# w5500.net
KiCad netlist of a schematic drawn in Altium Designer
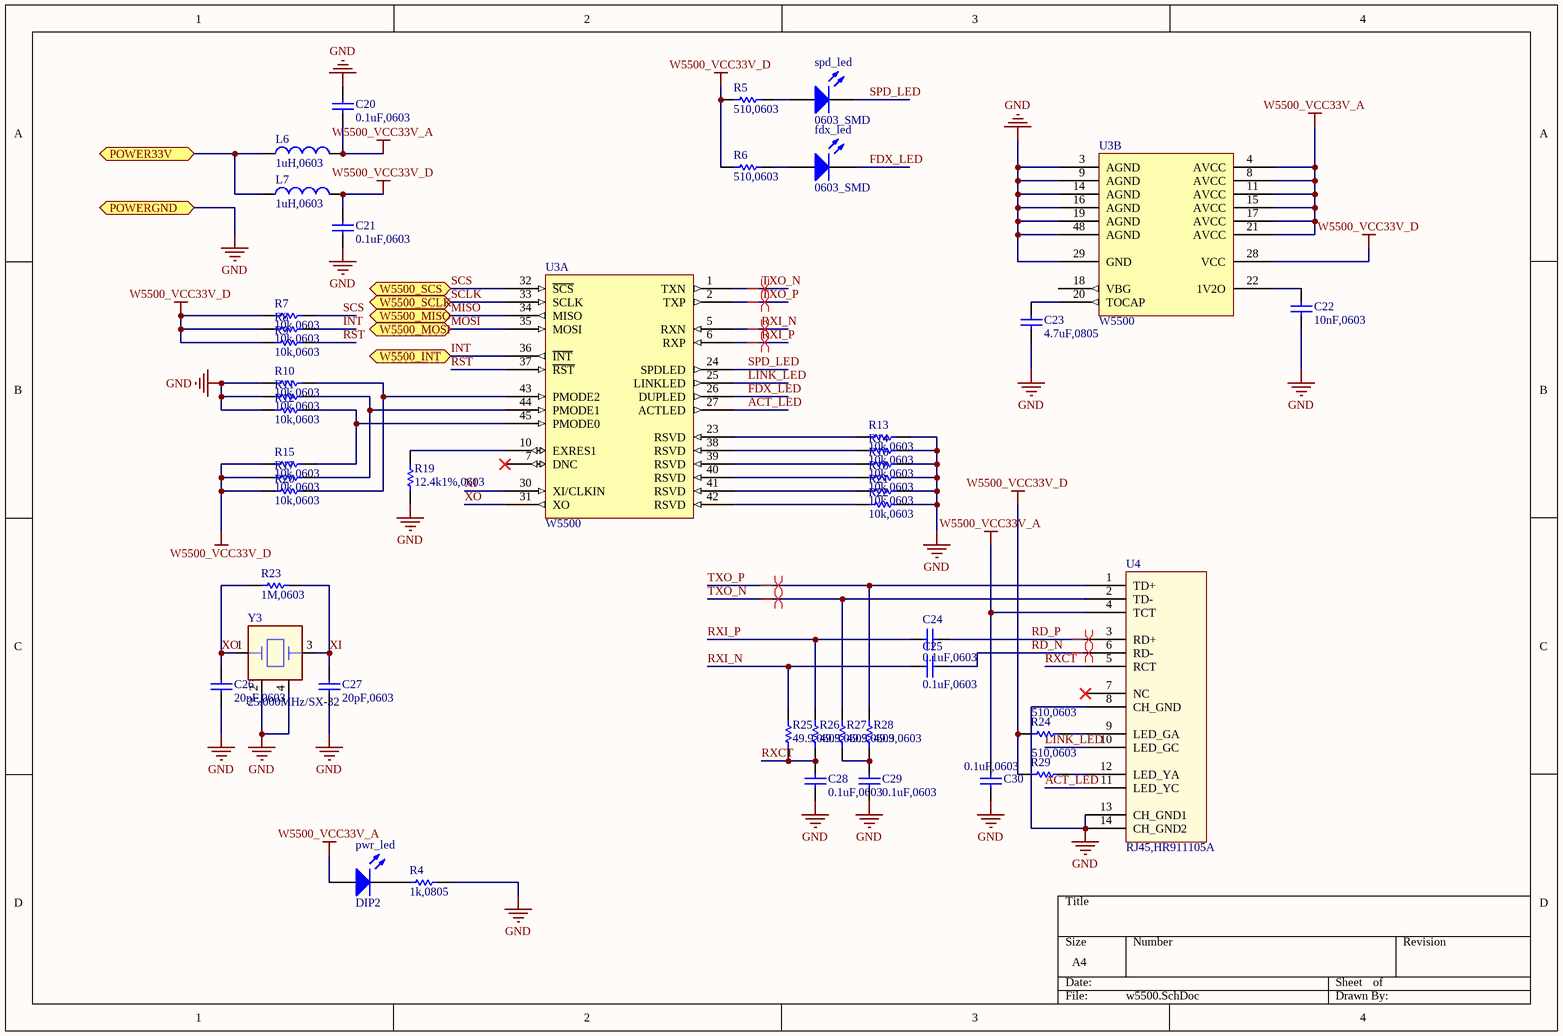
[diagram p0: w5500.SchDoc]

(export (version "E")
  (design (tool "Eeschema 10.0.6"))
  (components
    (comp (ref "C20")
      (value "0.1uF,0603")
      (footprint "C0603")
      (description "Capacitor")
      (fields (field (name "PUBLISHER") "Altium Limited"))
      (libsource (lib "Inte") (part "CAP"))
    )
    (comp (ref "C21")
      (value "0.1uF,0603")
      (footprint "C0603")
      (description "Capacitor")
      (fields (field (name "PUBLISHER") "Altium Limited"))
      (libsource (lib "Inte") (part "CAP"))
    )
    (comp (ref "C22")
      (value "10nF,0603")
      (footprint "C0603")
      (description "Capacitor")
      (fields (field (name "PUBLISHER") "Altium Limited"))
      (libsource (lib "Inte") (part "CAP"))
    )
    (comp (ref "C23")
      (value "4.7uF,0805")
      (footprint "C0805")
      (description "Capacitor")
      (fields (field (name "PUBLISHER") "Altium Limited"))
      (libsource (lib "Inte") (part "CAP"))
    )
    (comp (ref "C24")
      (value "0.1uF,0603")
      (footprint "C0603")
      (description "Capacitor")
      (fields (field (name "PUBLISHER") "Altium Limited"))
      (libsource (lib "Inte") (part "CAP"))
    )
    (comp (ref "C25")
      (value "0.1uF,0603")
      (footprint "C0603")
      (description "Capacitor")
      (fields (field (name "PUBLISHER") "Altium Limited"))
      (libsource (lib "Inte") (part "CAP"))
    )
    (comp (ref "C26")
      (value "20pF,0603")
      (footprint "C0603")
      (description "Capacitor")
      (fields (field (name "PUBLISHER") "Altium Limited"))
      (libsource (lib "Inte") (part "CAP"))
    )
    (comp (ref "C27")
      (value "20pF,0603")
      (footprint "C0603")
      (description "Capacitor")
      (fields (field (name "PUBLISHER") "Altium Limited"))
      (libsource (lib "Inte") (part "CAP"))
    )
    (comp (ref "C28")
      (value "0.1uF,0603")
      (footprint "C0603")
      (description "Capacitor")
      (fields (field (name "PUBLISHER") "Altium Limited"))
      (libsource (lib "Inte") (part "CAP"))
    )
    (comp (ref "C29")
      (value "0.1uF,0603")
      (footprint "C0603")
      (description "Capacitor")
      (fields (field (name "PUBLISHER") "Altium Limited"))
      (libsource (lib "Inte") (part "CAP"))
    )
    (comp (ref "C30")
      (value "0.1uF,0603")
      (footprint "C0603")
      (description "Capacitor")
      (fields (field (name "PUBLISHER") "Altium Limited"))
      (libsource (lib "Inte") (part "CAP"))
    )
    (comp (ref "fdx_led")
      (value "0603_SMD")
      (footprint "LED0805")
      (description "led")
      (libsource (lib "Inte") (part "LED"))
    )
    (comp (ref "L6")
      (value "1uH,0603")
      (footprint "L0603")
      (description "Inductor")
      (fields (field (name "PUBLISHER") "Altium Limited"))
      (libsource (lib "Inte") (part "Inductor"))
    )
    (comp (ref "L7")
      (value "1uH,0603")
      (footprint "L0603")
      (description "Inductor")
      (fields (field (name "PUBLISHER") "Altium Limited"))
      (libsource (lib "Inte") (part "Inductor"))
    )
    (comp (ref "pwr_led") (value "DIP2") (footprint "LEDDIP2") (libsource (lib "Inte") (part "LED")))
    (comp (ref "R4")
      (value "1k,0805")
      (footprint "R0805")
      (description "Resistor")
      (fields (field (name "PUBLISHER") "Altium Limited"))
      (libsource (lib "Inte") (part "Res1"))
    )
    (comp (ref "R5")
      (value "510,0603")
      (footprint "R0603")
      (description "Resistor")
      (fields (field (name "PUBLISHER") "Altium Limited"))
      (libsource (lib "Inte") (part "Res1"))
    )
    (comp (ref "R6")
      (value "510,0603")
      (footprint "R0603")
      (description "Resistor")
      (fields (field (name "PUBLISHER") "Altium Limited"))
      (libsource (lib "Inte") (part "Res1"))
    )
    (comp (ref "R7")
      (value "10k,0603")
      (footprint "R0603")
      (description "Resistor")
      (fields (field (name "PUBLISHER") "Altium Limited"))
      (libsource (lib "Inte") (part "Res1"))
    )
    (comp (ref "R8")
      (value "10k,0603")
      (footprint "R0603")
      (description "Resistor")
      (fields (field (name "PUBLISHER") "Altium Limited"))
      (libsource (lib "Inte") (part "Res1"))
    )
    (comp (ref "R9")
      (value "10k,0603")
      (footprint "R0603")
      (description "Resistor")
      (fields (field (name "PUBLISHER") "Altium Limited"))
      (libsource (lib "Inte") (part "Res1"))
    )
    (comp (ref "R10")
      (value "10k,0603")
      (footprint "R0603")
      (description "Resistor")
      (fields (field (name "PUBLISHER") "Altium Limited"))
      (libsource (lib "Inte") (part "Res1"))
    )
    (comp (ref "R11")
      (value "10k,0603")
      (footprint "R0603")
      (description "Resistor")
      (fields (field (name "PUBLISHER") "Altium Limited"))
      (libsource (lib "Inte") (part "Res1"))
    )
    (comp (ref "R12")
      (value "10k,0603")
      (footprint "R0603")
      (description "Resistor")
      (fields (field (name "PUBLISHER") "Altium Limited"))
      (libsource (lib "Inte") (part "Res1"))
    )
    (comp (ref "R13")
      (value "10k,0603")
      (footprint "R0603")
      (description "Resistor")
      (fields (field (name "PUBLISHER") "Altium Limited"))
      (libsource (lib "Inte") (part "Res1"))
    )
    (comp (ref "R14")
      (value "10k,0603")
      (footprint "R0603")
      (description "Resistor")
      (fields (field (name "PUBLISHER") "Altium Limited"))
      (libsource (lib "Inte") (part "Res1"))
    )
    (comp (ref "R15")
      (value "10k,0603")
      (footprint "R0603")
      (description "Resistor")
      (fields (field (name "PUBLISHER") "Altium Limited"))
      (libsource (lib "Inte") (part "Res1"))
    )
    (comp (ref "R16")
      (value "10k,0603")
      (footprint "R0603")
      (description "Resistor")
      (fields (field (name "PUBLISHER") "Altium Limited"))
      (libsource (lib "Inte") (part "Res1"))
    )
    (comp (ref "R17")
      (value "10k,0603")
      (footprint "R0603")
      (description "Resistor")
      (fields (field (name "PUBLISHER") "Altium Limited"))
      (libsource (lib "Inte") (part "Res1"))
    )
    (comp (ref "R18")
      (value "10k,0603")
      (footprint "R0603")
      (description "Resistor")
      (fields (field (name "PUBLISHER") "Altium Limited"))
      (libsource (lib "Inte") (part "Res1"))
    )
    (comp (ref "R19")
      (value "12.4k1%,0603")
      (footprint "R0603")
      (description "Resistor")
      (fields (field (name "PUBLISHER") "Altium Limited"))
      (libsource (lib "Inte") (part "Res1"))
    )
    (comp (ref "R20")
      (value "10k,0603")
      (footprint "R0603")
      (description "Resistor")
      (fields (field (name "PUBLISHER") "Altium Limited"))
      (libsource (lib "Inte") (part "Res1"))
    )
    (comp (ref "R21")
      (value "10k,0603")
      (footprint "R0603")
      (description "Resistor")
      (fields (field (name "PUBLISHER") "Altium Limited"))
      (libsource (lib "Inte") (part "Res1"))
    )
    (comp (ref "R22")
      (value "10k,0603")
      (footprint "R0603")
      (description "Resistor")
      (fields (field (name "PUBLISHER") "Altium Limited"))
      (libsource (lib "Inte") (part "Res1"))
    )
    (comp (ref "R23")
      (value "1M,0603")
      (footprint "R0603")
      (description "Resistor")
      (fields (field (name "PUBLISHER") "Altium Limited"))
      (libsource (lib "Inte") (part "Res1"))
    )
    (comp (ref "R24")
      (value "510,0603")
      (footprint "R0603")
      (description "Resistor")
      (fields (field (name "PUBLISHER") "Altium Limited"))
      (libsource (lib "Inte") (part "Res1"))
    )
    (comp (ref "R25")
      (value "49.9,0603")
      (footprint "R0603")
      (description "Resistor")
      (fields (field (name "PUBLISHER") "Altium Limited"))
      (libsource (lib "Inte") (part "Res1"))
    )
    (comp (ref "R26")
      (value "49.9,0603")
      (footprint "R0603")
      (description "Resistor")
      (fields (field (name "PUBLISHER") "Altium Limited"))
      (libsource (lib "Inte") (part "Res1"))
    )
    (comp (ref "R27")
      (value "49.9,0603")
      (footprint "R0603")
      (description "Resistor")
      (fields (field (name "PUBLISHER") "Altium Limited"))
      (libsource (lib "Inte") (part "Res1"))
    )
    (comp (ref "R28")
      (value "49.9,0603")
      (footprint "R0603")
      (description "Resistor")
      (fields (field (name "PUBLISHER") "Altium Limited"))
      (libsource (lib "Inte") (part "Res1"))
    )
    (comp (ref "R29")
      (value "510,0603")
      (footprint "R0603")
      (description "Resistor")
      (fields (field (name "PUBLISHER") "Altium Limited"))
      (libsource (lib "Inte") (part "Res1"))
    )
    (comp (ref "spd_led")
      (value "0603_SMD")
      (footprint "LED0805")
      (description "led")
      (libsource (lib "Inte") (part "LED"))
    )
    (comp (ref "U3") (value "W5500") (footprint "LQFP48") (libsource (lib "Inte") (part "W5500")))
    (comp (ref "U4") (value "RJ45,HR911105A") (footprint "RJ45") (libsource (lib "Inte") (part "HR911105A")))
    (comp (ref "Y3") (value "25.000MHz/SX-32") (footprint "3225") (libsource (lib "Inte") (part "CRYSTAL_5")))
  )
  (nets
    (net (code "1") (name "/ACT_LED") (class "Default")
      (node (ref "U3") (pin "27") (pinfunction "ACTLED_27") (pintype "output"))
      (node (ref "U4") (pin "11") (pinfunction "LED_YC_11") (pintype "passive"))
    )
    (net (code "2") (name "/FDX_LED") (class "Default")
      (node (ref "U3") (pin "26") (pinfunction "DUPLED_26") (pintype "output"))
      (node (ref "fdx_led") (pin "2") (pinfunction "K_2") (pintype "passive"))
    )
    (net (code "3") (name "/INT") (class "Default")
      (node (ref "R8") (pin "2") (pinfunction "2_2") (pintype "passive"))
      (node (ref "U3") (pin "36") (pinfunction "~{INT}_36") (pintype "output"))
    )
    (net (code "4") (name "/LINK_LED") (class "Default")
      (node (ref "U3") (pin "25") (pinfunction "LINKLED_25") (pintype "output"))
      (node (ref "U4") (pin "10") (pinfunction "LED_GC_10") (pintype "passive"))
    )
    (net (code "5") (name "/MISO") (class "Default")
      (node (ref "U3") (pin "34") (pinfunction "MISO_34") (pintype "output"))
    )
    (net (code "6") (name "/MOSI") (class "Default")
      (node (ref "U3") (pin "35") (pinfunction "MOSI_35") (pintype "input"))
    )
    (net (code "7") (name "/POWER33V") (class "Default")
      (node (ref "L6") (pin "1") (pinfunction "1_1") (pintype "passive"))
      (node (ref "L7") (pin "1") (pinfunction "1_1") (pintype "passive"))
    )
    (net (code "8") (name "/RD_N") (class "Default")
      (node (ref "C25") (pin "2") (pinfunction "2_2") (pintype "passive"))
      (node (ref "U4") (pin "6") (pinfunction "RD-_6") (pintype "passive"))
    )
    (net (code "9") (name "/RD_P") (class "Default")
      (node (ref "C24") (pin "2") (pinfunction "2_2") (pintype "passive"))
      (node (ref "U4") (pin "3") (pinfunction "RD+_3") (pintype "passive"))
    )
    (net (code "10") (name "/RST") (class "Default")
      (node (ref "R9") (pin "2") (pinfunction "2_2") (pintype "passive"))
      (node (ref "U3") (pin "37") (pinfunction "~{RST}_37") (pintype "input"))
    )
    (net (code "11") (name "/RXCT") (class "Default")
      (node (ref "C28") (pin "2") (pinfunction "2_2") (pintype "passive"))
      (node (ref "R25") (pin "1") (pinfunction "1_1") (pintype "passive"))
      (node (ref "R26") (pin "2") (pinfunction "2_2") (pintype "passive"))
      (node (ref "U4") (pin "5") (pinfunction "RCT_5") (pintype "passive"))
    )
    (net (code "12") (name "/RXI_N") (class "Default")
      (node (ref "C25") (pin "1") (pinfunction "1_1") (pintype "passive"))
      (node (ref "R25") (pin "2") (pinfunction "2_2") (pintype "passive"))
      (node (ref "U3") (pin "5") (pinfunction "RXN_5") (pintype "input"))
    )
    (net (code "13") (name "/RXI_P") (class "Default")
      (node (ref "C24") (pin "1") (pinfunction "1_1") (pintype "passive"))
      (node (ref "R26") (pin "1") (pinfunction "1_1") (pintype "passive"))
      (node (ref "U3") (pin "6") (pinfunction "RXP_6") (pintype "input"))
    )
    (net (code "14") (name "/SCLK") (class "Default")
      (node (ref "U3") (pin "33") (pinfunction "SCLK_33") (pintype "input"))
    )
    (net (code "15") (name "/SCS") (class "Default")
      (node (ref "R7") (pin "2") (pinfunction "2_2") (pintype "passive"))
      (node (ref "U3") (pin "32") (pinfunction "~{SCS}_32") (pintype "input"))
    )
    (net (code "16") (name "/SPD_LED") (class "Default")
      (node (ref "U3") (pin "24") (pinfunction "SPDLED_24") (pintype "output"))
      (node (ref "spd_led") (pin "2") (pinfunction "K_2") (pintype "passive"))
    )
    (net (code "17") (name "/TXO_N") (class "Default")
      (node (ref "R27") (pin "1") (pinfunction "1_1") (pintype "passive"))
      (node (ref "U3") (pin "1") (pinfunction "TXN_1") (pintype "output"))
      (node (ref "U4") (pin "2") (pinfunction "TD-_2") (pintype "passive"))
    )
    (net (code "18") (name "/TXO_P") (class "Default")
      (node (ref "R28") (pin "1") (pinfunction "1_1") (pintype "passive"))
      (node (ref "U3") (pin "2") (pinfunction "TXP_2") (pintype "output"))
      (node (ref "U4") (pin "1") (pinfunction "TD+_1") (pintype "passive"))
    )
    (net (code "19") (name "/XI") (class "Default")
      (node (ref "C27") (pin "1") (pinfunction "1_1") (pintype "passive"))
      (node (ref "R23") (pin "2") (pinfunction "2_2") (pintype "passive"))
      (node (ref "U3") (pin "30") (pinfunction "XI/CLKIN_30") (pintype "input"))
      (node (ref "Y3") (pin "3") (pinfunction "3_3") (pintype "passive"))
    )
    (net (code "20") (name "/XO") (class "Default")
      (node (ref "C26") (pin "1") (pinfunction "1_1") (pintype "passive"))
      (node (ref "R23") (pin "1") (pinfunction "1_1") (pintype "passive"))
      (node (ref "U3") (pin "31") (pinfunction "XO_31") (pintype "output"))
      (node (ref "Y3") (pin "1") (pinfunction "1_1") (pintype "passive"))
    )
    (net (code "21") (name "GND") (class "Default")
      (node (ref "C20") (pin "2") (pinfunction "2_2") (pintype "passive"))
      (node (ref "C21") (pin "1") (pinfunction "1_1") (pintype "passive"))
      (node (ref "C22") (pin "1") (pinfunction "1_1") (pintype "passive"))
      (node (ref "C23") (pin "1") (pinfunction "1_1") (pintype "passive"))
      (node (ref "C26") (pin "2") (pinfunction "2_2") (pintype "passive"))
      (node (ref "C27") (pin "2") (pinfunction "2_2") (pintype "passive"))
      (node (ref "C28") (pin "1") (pinfunction "1_1") (pintype "passive"))
      (node (ref "C29") (pin "2") (pinfunction "2_2") (pintype "passive"))
      (node (ref "C30") (pin "1") (pinfunction "1_1") (pintype "passive"))
      (node (ref "R10") (pin "1") (pinfunction "1_1") (pintype "passive"))
      (node (ref "R11") (pin "1") (pinfunction "1_1") (pintype "passive"))
      (node (ref "R12") (pin "1") (pinfunction "1_1") (pintype "passive"))
      (node (ref "R13") (pin "2") (pinfunction "2_2") (pintype "passive"))
      (node (ref "R14") (pin "2") (pinfunction "2_2") (pintype "passive"))
      (node (ref "R16") (pin "2") (pinfunction "2_2") (pintype "passive"))
      (node (ref "R18") (pin "2") (pinfunction "2_2") (pintype "passive"))
      (node (ref "R19") (pin "1") (pinfunction "1_1") (pintype "passive"))
      (node (ref "R21") (pin "2") (pinfunction "2_2") (pintype "passive"))
      (node (ref "R22") (pin "2") (pinfunction "2_2") (pintype "passive"))
      (node (ref "R4") (pin "2") (pinfunction "2_2") (pintype "passive"))
      (node (ref "U3") (pin "14") (pinfunction "AGND_14") (pintype "power_in"))
      (node (ref "U3") (pin "16") (pinfunction "AGND_16") (pintype "power_in"))
      (node (ref "U3") (pin "19") (pinfunction "AGND_19") (pintype "power_in"))
      (node (ref "U3") (pin "29") (pinfunction "GND_29") (pintype "power_in"))
      (node (ref "U3") (pin "3") (pinfunction "AGND_3") (pintype "power_in"))
      (node (ref "U3") (pin "48") (pinfunction "AGND_48") (pintype "power_in"))
      (node (ref "U3") (pin "9") (pinfunction "AGND_9") (pintype "power_in"))
      (node (ref "U4") (pin "13") (pinfunction "CH_GND1_13") (pintype "passive"))
      (node (ref "U4") (pin "14") (pinfunction "CH_GND2_14") (pintype "passive"))
      (node (ref "U4") (pin "8") (pinfunction "CH_GND_8") (pintype "passive"))
      (node (ref "Y3") (pin "2") (pinfunction "2_2") (pintype "passive"))
      (node (ref "Y3") (pin "4") (pinfunction "4_4") (pintype "passive"))
    )
    (net (code "22") (name "Net-(C29-Pad1)") (class "Default")
      (node (ref "C29") (pin "1") (pinfunction "1_1") (pintype "passive"))
      (node (ref "R27") (pin "2") (pinfunction "2_2") (pintype "passive"))
      (node (ref "R28") (pin "2") (pinfunction "2_2") (pintype "passive"))
    )
    (net (code "23") (name "Net-(R13-Pad1)") (class "Default")
      (node (ref "R13") (pin "1") (pinfunction "1_1") (pintype "passive"))
      (node (ref "U3") (pin "23") (pinfunction "RSVD_23") (pintype "input"))
    )
    (net (code "24") (name "Net-(R14-Pad1)") (class "Default")
      (node (ref "R14") (pin "1") (pinfunction "1_1") (pintype "passive"))
      (node (ref "U3") (pin "38") (pinfunction "RSVD_38") (pintype "input"))
    )
    (net (code "25") (name "Net-(R16-Pad1)") (class "Default")
      (node (ref "R16") (pin "1") (pinfunction "1_1") (pintype "passive"))
      (node (ref "U3") (pin "39") (pinfunction "RSVD_39") (pintype "input"))
    )
    (net (code "26") (name "Net-(R18-Pad1)") (class "Default")
      (node (ref "R18") (pin "1") (pinfunction "1_1") (pintype "passive"))
      (node (ref "U3") (pin "40") (pinfunction "RSVD_40") (pintype "input"))
    )
    (net (code "27") (name "Net-(R21-Pad1)") (class "Default")
      (node (ref "R21") (pin "1") (pinfunction "1_1") (pintype "passive"))
      (node (ref "U3") (pin "41") (pinfunction "RSVD_41") (pintype "input"))
    )
    (net (code "28") (name "Net-(R22-Pad1)") (class "Default")
      (node (ref "R22") (pin "1") (pinfunction "1_1") (pintype "passive"))
      (node (ref "U3") (pin "42") (pinfunction "RSVD_42") (pintype "input"))
    )
    (net (code "29") (name "Net-(U3A-EXRES1)") (class "Default")
      (node (ref "R19") (pin "2") (pinfunction "2_2") (pintype "passive"))
      (node (ref "U3") (pin "10") (pinfunction "EXRES1_10") (pintype "bidirectional"))
    )
    (net (code "30") (name "Net-(U3A-PMODE0)") (class "Default")
      (node (ref "R12") (pin "2") (pinfunction "2_2") (pintype "passive"))
      (node (ref "R15") (pin "2") (pinfunction "2_2") (pintype "passive"))
      (node (ref "U3") (pin "45") (pinfunction "PMODE0_45") (pintype "input"))
    )
    (net (code "31") (name "Net-(U3A-PMODE1)") (class "Default")
      (node (ref "R11") (pin "2") (pinfunction "2_2") (pintype "passive"))
      (node (ref "R17") (pin "2") (pinfunction "2_2") (pintype "passive"))
      (node (ref "U3") (pin "44") (pinfunction "PMODE1_44") (pintype "input"))
    )
    (net (code "32") (name "Net-(U3A-PMODE2)") (class "Default")
      (node (ref "R10") (pin "2") (pinfunction "2_2") (pintype "passive"))
      (node (ref "R20") (pin "2") (pinfunction "2_2") (pintype "passive"))
      (node (ref "U3") (pin "43") (pinfunction "PMODE2_43") (pintype "input"))
    )
    (net (code "33") (name "Net-(U3B-1V2O)") (class "Default")
      (node (ref "C22") (pin "2") (pinfunction "2_2") (pintype "passive"))
      (node (ref "U3") (pin "22") (pinfunction "1V2O_22") (pintype "power_in"))
    )
    (net (code "34") (name "Net-(U3B-TOCAP)") (class "Default")
      (node (ref "C23") (pin "2") (pinfunction "2_2") (pintype "passive"))
      (node (ref "U3") (pin "20") (pinfunction "TOCAP_20") (pintype "output"))
    )
    (net (code "35") (name "Net-(U4-LED_GA)") (class "Default")
      (node (ref "R24") (pin "2") (pinfunction "2_2") (pintype "passive"))
      (node (ref "U4") (pin "9") (pinfunction "LED_GA_9") (pintype "passive"))
    )
    (net (code "36") (name "Net-(U4-LED_YA)") (class "Default")
      (node (ref "R29") (pin "2") (pinfunction "2_2") (pintype "passive"))
      (node (ref "U4") (pin "12") (pinfunction "LED_YA_12") (pintype "passive"))
    )
    (net (code "37") (name "Net-(fdx_led-A)") (class "Default")
      (node (ref "R6") (pin "2") (pinfunction "2_2") (pintype "passive"))
      (node (ref "fdx_led") (pin "1") (pinfunction "A_1") (pintype "passive"))
    )
    (net (code "38") (name "Net-(pwr_led-K)") (class "Default")
      (node (ref "R4") (pin "1") (pinfunction "1_1") (pintype "passive"))
      (node (ref "pwr_led") (pin "2") (pinfunction "K_2") (pintype "passive"))
    )
    (net (code "39") (name "Net-(spd_led-A)") (class "Default")
      (node (ref "R5") (pin "2") (pinfunction "2_2") (pintype "passive"))
      (node (ref "spd_led") (pin "1") (pinfunction "A_1") (pintype "passive"))
    )
    (net (code "40") (name "W5500_VCC33V_A") (class "Default")
      (node (ref "C20") (pin "1") (pinfunction "1_1") (pintype "passive"))
      (node (ref "C30") (pin "2") (pinfunction "2_2") (pintype "passive"))
      (node (ref "L6") (pin "2") (pinfunction "2_2") (pintype "passive"))
      (node (ref "U3") (pin "11") (pinfunction "AVCC_11") (pintype "power_in"))
      (node (ref "U3") (pin "15") (pinfunction "AVCC_15") (pintype "power_in"))
      (node (ref "U3") (pin "17") (pinfunction "AVCC_17") (pintype "power_in"))
      (node (ref "U3") (pin "21") (pinfunction "AVCC_21") (pintype "power_in"))
      (node (ref "U3") (pin "4") (pinfunction "AVCC_4") (pintype "power_in"))
      (node (ref "U3") (pin "8") (pinfunction "AVCC_8") (pintype "power_in"))
      (node (ref "U4") (pin "4") (pinfunction "TCT_4") (pintype "passive"))
      (node (ref "pwr_led") (pin "1") (pinfunction "A_1") (pintype "passive"))
    )
    (net (code "41") (name "W5500_VCC33V_D") (class "Default")
      (node (ref "C21") (pin "2") (pinfunction "2_2") (pintype "passive"))
      (node (ref "L7") (pin "2") (pinfunction "2_2") (pintype "passive"))
      (node (ref "R15") (pin "1") (pinfunction "1_1") (pintype "passive"))
      (node (ref "R17") (pin "1") (pinfunction "1_1") (pintype "passive"))
      (node (ref "R20") (pin "1") (pinfunction "1_1") (pintype "passive"))
      (node (ref "R24") (pin "1") (pinfunction "1_1") (pintype "passive"))
      (node (ref "R29") (pin "1") (pinfunction "1_1") (pintype "passive"))
      (node (ref "R5") (pin "1") (pinfunction "1_1") (pintype "passive"))
      (node (ref "R6") (pin "1") (pinfunction "1_1") (pintype "passive"))
      (node (ref "R7") (pin "1") (pinfunction "1_1") (pintype "passive"))
      (node (ref "R8") (pin "1") (pinfunction "1_1") (pintype "passive"))
      (node (ref "R9") (pin "1") (pinfunction "1_1") (pintype "passive"))
      (node (ref "U3") (pin "28") (pinfunction "VCC_28") (pintype "power_in"))
    )
    (net (code "42") (name "unconnected-(U3A-DNC-Pad7)") (class "Default")
      (node (ref "U3") (pin "7") (pinfunction "DNC_7") (pintype "bidirectional+no_connect"))
    )
    (net (code "43") (name "unconnected-(U3B-VBG-Pad18)") (class "Default")
      (node (ref "U3") (pin "18") (pinfunction "VBG_18") (pintype "output"))
    )
    (net (code "44") (name "unconnected-(U4-NC-Pad7)") (class "Default")
      (node (ref "U4") (pin "7") (pinfunction "NC_7") (pintype "passive+no_connect"))
    )
  )
)
